# extBoard_sheet2_acc.net
KiCad netlist of a schematic drawn in Altium Designer
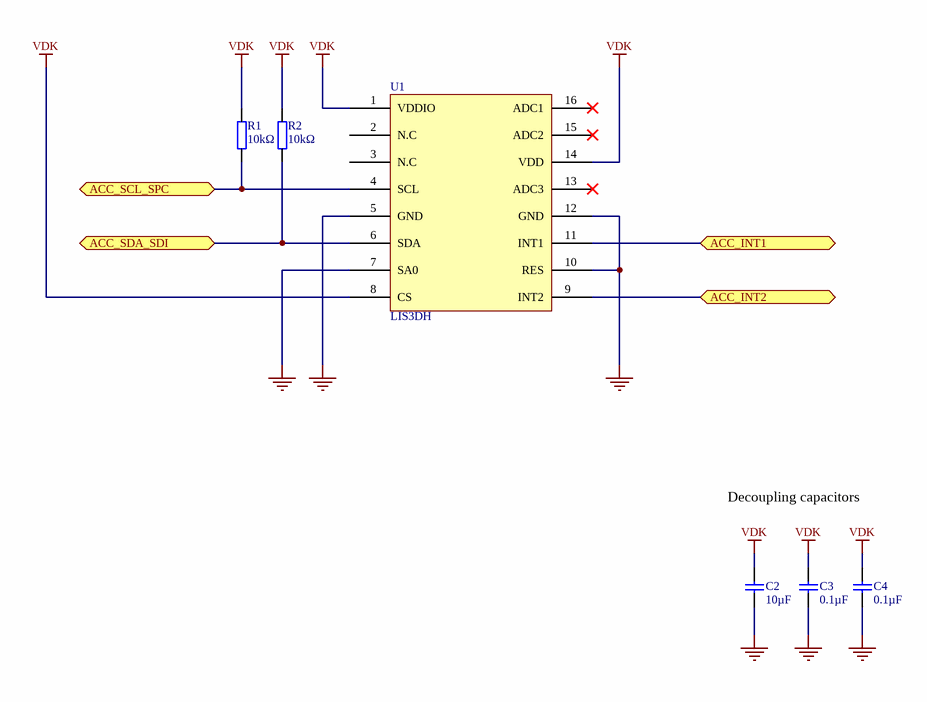
[diagram p0: extBoard_sheet2_acc.SchDoc]

(export (version "E")
  (design (tool "Eeschema 10.0.6"))
  (components
    (comp (ref "C2")
      (value "10µF")
      (footprint "CAPC2012X11L")
      (description "Capacitor, X5R, ±10%")
      (fields (field (name "PART NUMBER") "C0805-4µ7") (field (name "PUBLISHER") "Nordic Semiconductor"))
      (libsource (lib "pca10056") (part "CAP_0805"))
    )
    (comp (ref "C3")
      (value "0.1µF")
      (footprint "CAPC2012X11L")
      (description "Capacitor, X5R, ±10%")
      (fields (field (name "PART NUMBER") "C0805-4µ7") (field (name "PUBLISHER") "Nordic Semiconductor"))
      (libsource (lib "pca10056") (part "CAP_0805"))
    )
    (comp (ref "C4")
      (value "0.1µF")
      (footprint "CAPC2012X11L")
      (description "Capacitor, X5R, ±10%")
      (fields (field (name "PART NUMBER") "C0805-4µ7") (field (name "PUBLISHER") "Nordic Semiconductor"))
      (libsource (lib "pca10056") (part "CAP_0805"))
    )
    (comp (ref "R1") (value "10kΩ") (footprint "R0805") (libsource (lib "extBoardLib") (part "R0805")))
    (comp (ref "R2") (value "10kΩ") (footprint "R0805") (libsource (lib "extBoardLib") (part "R0805")))
    (comp (ref "U1")
      (value "LIS3DH")
      (footprint "LGA-16 (3x3x1.0mm)")
      (libsource (lib "extBoardLib") (part "LIS3DH"))
    )
  )
  (nets
    (net (code "1") (name "/ACC_INT1") (class "Default")
      (node (ref "U1") (pin "11") (pinfunction "INT1_11") (pintype "passive"))
    )
    (net (code "2") (name "/ACC_INT2") (class "Default")
      (node (ref "U1") (pin "9") (pinfunction "INT2_9") (pintype "passive"))
    )
    (net (code "3") (name "/ACC_SCL_SPC") (class "Default")
      (node (ref "R1") (pin "1") (pinfunction "1_1") (pintype "passive"))
      (node (ref "U1") (pin "4") (pinfunction "SCL_4") (pintype "passive"))
    )
    (net (code "4") (name "/ACC_SDA_SDI") (class "Default")
      (node (ref "R2") (pin "1") (pinfunction "1_1") (pintype "passive"))
      (node (ref "U1") (pin "6") (pinfunction "SDA_6") (pintype "passive"))
    )
    (net (code "5") (name "GND") (class "Default")
      (node (ref "C2") (pin "1") (pinfunction "1_1") (pintype "passive"))
      (node (ref "C3") (pin "1") (pinfunction "1_1") (pintype "passive"))
      (node (ref "C4") (pin "1") (pinfunction "1_1") (pintype "passive"))
      (node (ref "U1") (pin "10") (pinfunction "RES_10") (pintype "passive"))
      (node (ref "U1") (pin "12") (pinfunction "GND_12") (pintype "passive"))
      (node (ref "U1") (pin "5") (pinfunction "GND_5") (pintype "passive"))
      (node (ref "U1") (pin "7") (pinfunction "SA0_7") (pintype "passive"))
    )
    (net (code "6") (name "VDK") (class "Default")
      (node (ref "C2") (pin "2") (pinfunction "2_2") (pintype "passive"))
      (node (ref "C3") (pin "2") (pinfunction "2_2") (pintype "passive"))
      (node (ref "C4") (pin "2") (pinfunction "2_2") (pintype "passive"))
      (node (ref "R1") (pin "2") (pinfunction "2_2") (pintype "passive"))
      (node (ref "R2") (pin "2") (pinfunction "2_2") (pintype "passive"))
      (node (ref "U1") (pin "1") (pinfunction "VDDIO_1") (pintype "passive"))
      (node (ref "U1") (pin "14") (pinfunction "VDD_14") (pintype "passive"))
      (node (ref "U1") (pin "8") (pinfunction "CS_8") (pintype "passive"))
    )
    (net (code "7") (name "unconnected-(U1-ADC1-Pad16)") (class "Default")
      (node (ref "U1") (pin "16") (pinfunction "ADC1_16") (pintype "passive+no_connect"))
    )
    (net (code "8") (name "unconnected-(U1-ADC2-Pad15)") (class "Default")
      (node (ref "U1") (pin "15") (pinfunction "ADC2_15") (pintype "passive+no_connect"))
    )
    (net (code "9") (name "unconnected-(U1-ADC3-Pad13)") (class "Default")
      (node (ref "U1") (pin "13") (pinfunction "ADC3_13") (pintype "passive+no_connect"))
    )
    (net (code "10") (name "unconnected-(U1-N.C-Pad2)") (class "Default")
      (node (ref "U1") (pin "2") (pinfunction "N.C_2") (pintype "passive"))
    )
    (net (code "11") (name "unconnected-(U1-N.C-Pad3)") (class "Default")
      (node (ref "U1") (pin "3") (pinfunction "N.C_3") (pintype "passive"))
    )
  )
)
